# Power_Supply.net
KiCad netlist of a schematic drawn in Altium Designer
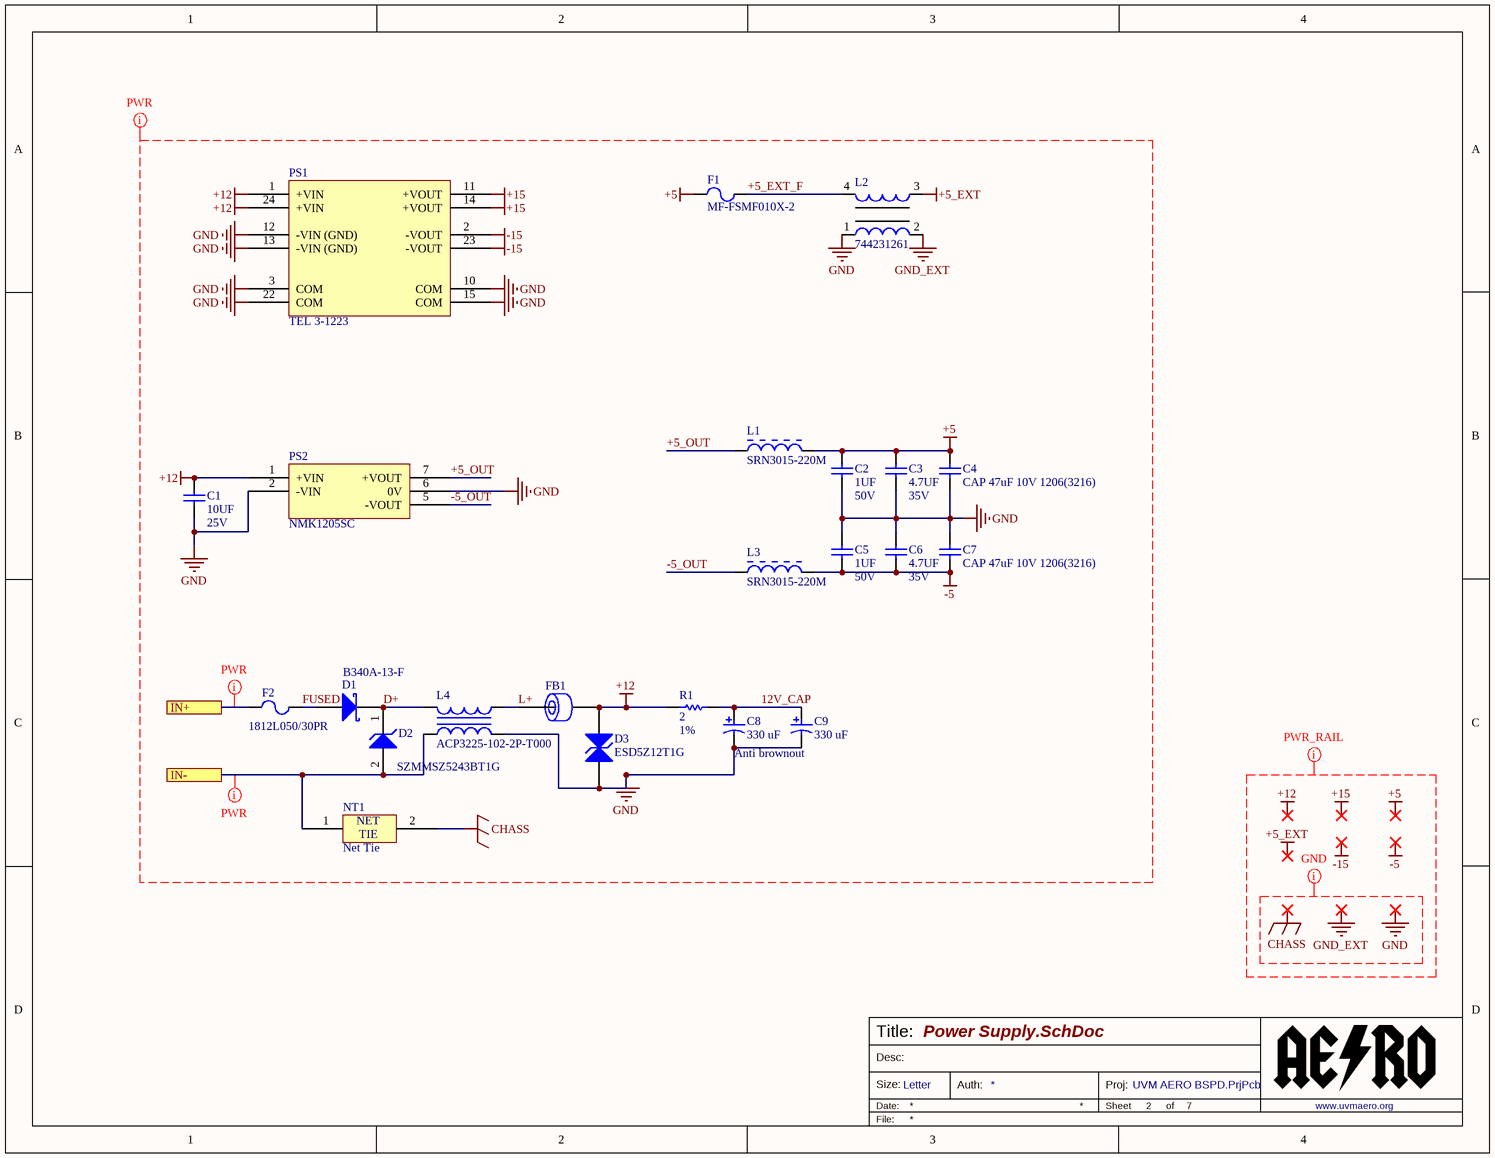
[diagram p0: Power Supply.SchDoc]

(export (version "E")
  (design (tool "Eeschema 10.0.6"))
  (components
    (comp (ref "C1")
      (value "CAP 0603 10UF 25V 20% X5R")
      (footprint "0603_CAP")
      (description "Capacitor Surface Mount 0603 Footprint 10UF 25V 20% Tolerance Ceramic X5R")
      (fields
        (field (name "VAL") "10UF")
        (field (name "VOL") "25V")
        (field (name "MANUFACTURER") "Various")
        (field (name "VOLTAGE") "25V")
      )
      (libsource (lib "Passive Components") (part "cap"))
    )
    (comp (ref "C2")
      (value "CAP 0603 1UF 50V 10% X7R")
      (footprint "0603_CAP")
      (description "Capacitor Surface Mount 0603 Footprint 1UF 50V 10% Tolerance Ceramic X7R")
      (fields
        (field (name "VAL") "1UF")
        (field (name "VOL") "50V")
        (field (name "MANUFACTURER") "Various")
        (field (name "VOLTAGE") "50V")
      )
      (libsource (lib "Passive Components") (part "cap"))
    )
    (comp (ref "C3")
      (value "CAP 0805 4.7UF 35V 10% X7R")
      (footprint "0805_CAP")
      (description "Capacitor Surface Mount 0805 Footprint 4.7UF 35V 10% Tolerance Ceramic X7R")
      (fields
        (field (name "VAL") "4.7UF")
        (field (name "VOL") "35V")
        (field (name "MANUFACTURER") "Various")
        (field (name "VOLTAGE") "35V")
      )
      (libsource (lib "Passive Components") (part "cap"))
    )
    (comp (ref "C4")
      (value "CAP 47uF 10V 1206(3216)")
      (footprint "CAPC1206(3216)190_N")
      (description "CAP 47uF 10V ±20% 1206 (3216 Metric) Thickness 1.9mm SMD")
      (fields (field (name "TOLERANCE") "Â±20%"))
      (libsource (lib "Altium Content Vault") (part "CAP"))
    )
    (comp (ref "C5")
      (value "CAP 0603 1UF 50V 10% X7R")
      (footprint "0603_CAP")
      (description "Capacitor Surface Mount 0603 Footprint 1UF 50V 10% Tolerance Ceramic X7R")
      (fields
        (field (name "VAL") "1UF")
        (field (name "VOL") "50V")
        (field (name "MANUFACTURER") "Various")
        (field (name "VOLTAGE") "50V")
      )
      (libsource (lib "Passive Components") (part "cap"))
    )
    (comp (ref "C6")
      (value "CAP 0805 4.7UF 35V 10% X7R")
      (footprint "0805_CAP")
      (description "Capacitor Surface Mount 0805 Footprint 4.7UF 35V 10% Tolerance Ceramic X7R")
      (fields
        (field (name "VAL") "4.7UF")
        (field (name "VOL") "35V")
        (field (name "MANUFACTURER") "Various")
        (field (name "VOLTAGE") "35V")
      )
      (libsource (lib "Passive Components") (part "cap"))
    )
    (comp (ref "C7")
      (value "CAP 47uF 10V 1206(3216)")
      (footprint "CAPC1206(3216)190_N")
      (description "CAP 47uF 10V ±20% 1206 (3216 Metric) Thickness 1.9mm SMD")
      (fields (field (name "TOLERANCE") "Â±20%"))
      (libsource (lib "Altium Content Vault") (part "CAP"))
    )
    (comp (ref "C8")
      (value "UUD1V331MNL1GS")
      (footprint "NIC-CAPA2-10X10_V")
      (fields (field (name "MANUFACTURER") "Nichicon") (field (name "RATED CAPACITANCE") "330 uF"))
      (libsource (lib "AERO Parts") (part "UUD1V331MNL1GS"))
    )
    (comp (ref "C9")
      (value "UUD1V331MNL1GS")
      (footprint "NIC-CAPA2-10X10_V")
      (fields (field (name "MANUFACTURER") "Nichicon") (field (name "RATED CAPACITANCE") "330 uF"))
      (libsource (lib "AERO Parts") (part "UUD1V331MNL1GS"))
    )
    (comp (ref "D1")
      (value "B340A-13-F")
      (footprint "DIOD-SMA-2_V")
      (libsource (lib "Altium Content Vault") (part "DSKY-AK-2"))
    )
    (comp (ref "D2")
      (value "SZMMSZ5243BT1G")
      (footprint "ONSC-SOD-123-2-425-04_V")
      (description "Zener Voltage Regulator, 500 mW, 2-Pin SOD-123, Pb-Free, Tape and Reel")
      (fields (field (name "MANUFACTURER") "On Semiconductor"))
      (libsource (lib "Altium Content Vault") (part "ONSC-K1A2-2"))
    )
    (comp (ref "D3")
      (value "ESD5Z12T1G")
      (footprint "ONSC-SOD-523-2-502-01_V")
      (fields (field (name "MANUFACTURER") "On Semiconductor"))
      (libsource (lib "bspd parts") (part "ESD5Z12T1G"))
    )
    (comp (ref "F1")
      (value "MF-FSMF010X-2")
      (footprint "MF-FSMF")
      (description "Polymeric PTC Resettable Fuse 15V 100mA Ih Surface Mount 0603 (1608 Metric), Concave")
      (libsource (lib "bspd parts") (part "MF-FSMF010X-2"))
    )
    (comp (ref "F2")
      (value "1812L050/30PR")
      (footprint "LFUS-1812L05030PR")
      (description "PTC Resettable Fuse, 0.8 W, 30 V, -40 to 85 degC, 2-Pin SMD, RoHS, Tape and Reel")
      (fields (field (name "MANUFACTURER") "Littelfuse-Inc."))
      (libsource (lib "bspd parts") (part "1812L050/30PR"))
    )
    (comp (ref "FB1")
      (value "Ferrite Chip 1500 Ohms")
      (footprint "0805")
      (description "Ferrite Chip 1000 mA 1500 Ohms Differential Mode - Single 0805 Footprint")
      (fields (field (name "MANUFACTURER") "Wurth Electronics"))
      (libsource (lib "Passive Components") (part "Ferrite Bead"))
    )
    (comp (ref "L1")
      (value "SRN3015-220M")
      (footprint "SRN3015-2_V")
      (fields (field (name "MANUFACTURER") "Bourns"))
      (libsource (lib "bspd parts") (part "SRN3015-220M"))
    )
    (comp (ref "L2")
      (value "744231261")
      (footprint "WE-CNSW-0805")
      (description "SMD Common Mode Noise Suppressor WE-CNSW, Z = 260 Ohm")
      (libsource (lib "Altium Content Vault") (part "PAS-IND-INDUCTOR-4A"))
    )
    (comp (ref "L3")
      (value "SRN3015-220M")
      (footprint "SRN3015-2_V")
      (fields (field (name "MANUFACTURER") "Bourns"))
      (libsource (lib "bspd parts") (part "SRN3015-220M"))
    )
    (comp (ref "L4")
      (value "ACP3225-102-2P-T000")
      (footprint "TDK-ACP3225-102-2P-T000-4_V")
      (fields (field (name "MANUFACTURER") "TDK"))
      (libsource (lib "bspd parts") (part "ACP3225-102-2P-T000"))
    )
    (comp (ref "NT1")
      (value "Net Tie")
      (footprint "20MIL_TIE")
      (description "Net Tie (No BOM)")
      (libsource (lib "bspd parts") (part "NET TIE"))
    )
    (comp (ref "PS1")
      (value "TEL 3-1223")
      (footprint "TEL 3-1223")
      (description "Isolated Module DC DC Converter 2 Output 15V -15V   100mA, 100mA 9V - 18V Input")
      (libsource (lib "bspd parts") (part "TEL 3-1223"))
    )
    (comp (ref "PS2")
      (value "NMK1205SC")
      (footprint "NMV0505SC")
      (description "Isolated Module DC DC Converter 2 Output 5V -5V   200mA, 200mA 10.8V - 13.2V Input")
      (libsource (lib "bspd parts") (part "NMK1205SC"))
    )
    (comp (ref "R1")
      (value "RES 0805 2 1%")
      (footprint "0805_RES")
      (description "Resistor Surface Mount, 2 Ohms, 0805 Footprint, 1% Tolerance 0.125W")
      (fields
        (field (name "VAL") "2")
        (field (name "TOL") "1%")
        (field (name "MANUFACTURER") "Various")
        (field (name "TOLERANCE") "1%")
      )
      (libsource (lib "Passive Components") (part "res"))
    )
  )
  (nets
    (net (code "1") (name "+5") (class "Default")
      (node (ref "C2") (pin "2") (pinfunction "2_2") (pintype "passive"))
      (node (ref "C3") (pin "2") (pinfunction "2_2") (pintype "passive"))
      (node (ref "C4") (pin "2") (pinfunction "2_2") (pintype "passive"))
      (node (ref "F1") (pin "1") (pinfunction "1_1") (pintype "passive"))
      (node (ref "L1") (pin "2") (pinfunction "2_2") (pintype "passive"))
    )
    (net (code "2") (name "+5_EXT") (class "Default")
      (node (ref "L2") (pin "3") (pinfunction "3_3") (pintype "passive"))
    )
    (net (code "3") (name "+12") (class "Default")
      (node (ref "C1") (pin "2") (pinfunction "2_2") (pintype "passive"))
      (node (ref "D3") (pin "1") (pinfunction "A1_1") (pintype "passive"))
      (node (ref "FB1") (pin "2") (pinfunction "2_2") (pintype "passive"))
      (node (ref "PS1") (pin "1") (pinfunction "+VIN_1") (pintype "power_in"))
      (node (ref "PS1") (pin "24") (pinfunction "+VIN_24") (pintype "power_in"))
      (node (ref "PS2") (pin "1") (pinfunction "+VIN_1") (pintype "power_in"))
      (node (ref "R1") (pin "1") (pinfunction "1_1") (pintype "passive"))
    )
    (net (code "4") (name "+15") (class "Default")
      (node (ref "PS1") (pin "11") (pinfunction "+VOUT_11") (pintype "power_in"))
      (node (ref "PS1") (pin "14") (pinfunction "+VOUT_14") (pintype "power_in"))
    )
    (net (code "5") (name "-5") (class "Default")
      (node (ref "C5") (pin "1") (pinfunction "1_1") (pintype "passive"))
      (node (ref "C6") (pin "1") (pinfunction "1_1") (pintype "passive"))
      (node (ref "C7") (pin "1") (pinfunction "1_1") (pintype "passive"))
      (node (ref "L3") (pin "2") (pinfunction "2_2") (pintype "passive"))
    )
    (net (code "6") (name "-15") (class "Default")
      (node (ref "PS1") (pin "2") (pinfunction "-VOUT_2") (pintype "power_in"))
      (node (ref "PS1") (pin "23") (pinfunction "-VOUT_23") (pintype "power_in"))
    )
    (net (code "7") (name "/+5_EXT_F") (class "Default")
      (node (ref "F1") (pin "2") (pinfunction "2_2") (pintype "passive"))
      (node (ref "L2") (pin "4") (pinfunction "4_4") (pintype "passive"))
    )
    (net (code "8") (name "/+5_OUT") (class "Default")
      (node (ref "L1") (pin "1") (pinfunction "1_1") (pintype "passive"))
      (node (ref "PS2") (pin "7") (pinfunction "+VOUT_7") (pintype "power_in"))
    )
    (net (code "9") (name "/-5_OUT") (class "Default")
      (node (ref "L3") (pin "1") (pinfunction "1_1") (pintype "passive"))
      (node (ref "PS2") (pin "5") (pinfunction "-VOUT_5") (pintype "power_in"))
    )
    (net (code "10") (name "/12V_CAP") (class "Default")
      (node (ref "C8") (pin "1") (pinfunction "1_1") (pintype "passive"))
      (node (ref "C9") (pin "1") (pinfunction "1_1") (pintype "passive"))
      (node (ref "R1") (pin "2") (pinfunction "2_2") (pintype "passive"))
    )
    (net (code "11") (name "/D+") (class "Default")
      (node (ref "D1") (pin "2") (pinfunction "K_2") (pintype "passive"))
      (node (ref "D2") (pin "1") (pinfunction "K_1") (pintype "passive"))
      (node (ref "L4") (pin "1") (pinfunction "1_1") (pintype "passive"))
    )
    (net (code "12") (name "/FUSED") (class "Default")
      (node (ref "D1") (pin "1") (pinfunction "A_1") (pintype "passive"))
      (node (ref "F2") (pin "2") (pinfunction "2_2") (pintype "passive"))
    )
    (net (code "13") (name "/IN+") (class "Default")
      (node (ref "F2") (pin "1") (pinfunction "1_1") (pintype "passive"))
    )
    (net (code "14") (name "/IN-") (class "Default")
      (node (ref "D2") (pin "2") (pinfunction "A_2") (pintype "passive"))
      (node (ref "L4") (pin "2") (pinfunction "2_2") (pintype "passive"))
      (node (ref "NT1") (pin "1") (pintype "passive"))
    )
    (net (code "15") (name "/L+") (class "Default")
      (node (ref "FB1") (pin "1") (pinfunction "1_1") (pintype "passive"))
      (node (ref "L4") (pin "4") (pinfunction "4_4") (pintype "passive"))
    )
    (net (code "16") (name "CHASS") (class "Default") (node (ref "NT1") (pin "2") (pintype "passive")))
    (net (code "17") (name "GND") (class "Default")
      (node (ref "C1") (pin "1") (pinfunction "1_1") (pintype "passive"))
      (node (ref "C2") (pin "1") (pinfunction "1_1") (pintype "passive"))
      (node (ref "C3") (pin "1") (pinfunction "1_1") (pintype "passive"))
      (node (ref "C4") (pin "1") (pinfunction "1_1") (pintype "passive"))
      (node (ref "C5") (pin "2") (pinfunction "2_2") (pintype "passive"))
      (node (ref "C6") (pin "2") (pinfunction "2_2") (pintype "passive"))
      (node (ref "C7") (pin "2") (pinfunction "2_2") (pintype "passive"))
      (node (ref "C8") (pin "2") (pinfunction "2_2") (pintype "passive"))
      (node (ref "C9") (pin "2") (pinfunction "2_2") (pintype "passive"))
      (node (ref "D3") (pin "2") (pinfunction "A2_2") (pintype "passive"))
      (node (ref "L2") (pin "1") (pinfunction "1_1") (pintype "passive"))
      (node (ref "L4") (pin "3") (pinfunction "3_3") (pintype "passive"))
      (node (ref "PS1") (pin "10") (pinfunction "COM_10") (pintype "power_in"))
      (node (ref "PS1") (pin "12") (pinfunction "-VIN_(GND)_12") (pintype "power_in"))
      (node (ref "PS1") (pin "13") (pinfunction "-VIN_(GND)_13") (pintype "power_in"))
      (node (ref "PS1") (pin "15") (pinfunction "COM_15") (pintype "power_in"))
      (node (ref "PS1") (pin "22") (pinfunction "COM_22") (pintype "power_in"))
      (node (ref "PS1") (pin "3") (pinfunction "COM_3") (pintype "power_in"))
      (node (ref "PS2") (pin "2") (pinfunction "-VIN_2") (pintype "power_in"))
      (node (ref "PS2") (pin "6") (pinfunction "0V_6") (pintype "power_in"))
    )
    (net (code "18") (name "GND_EXT") (class "Default")
      (node (ref "L2") (pin "2") (pinfunction "2_2") (pintype "passive"))
    )
  )
)
